# Diff_LPF.net
KiCad netlist of a schematic drawn in EAGLE
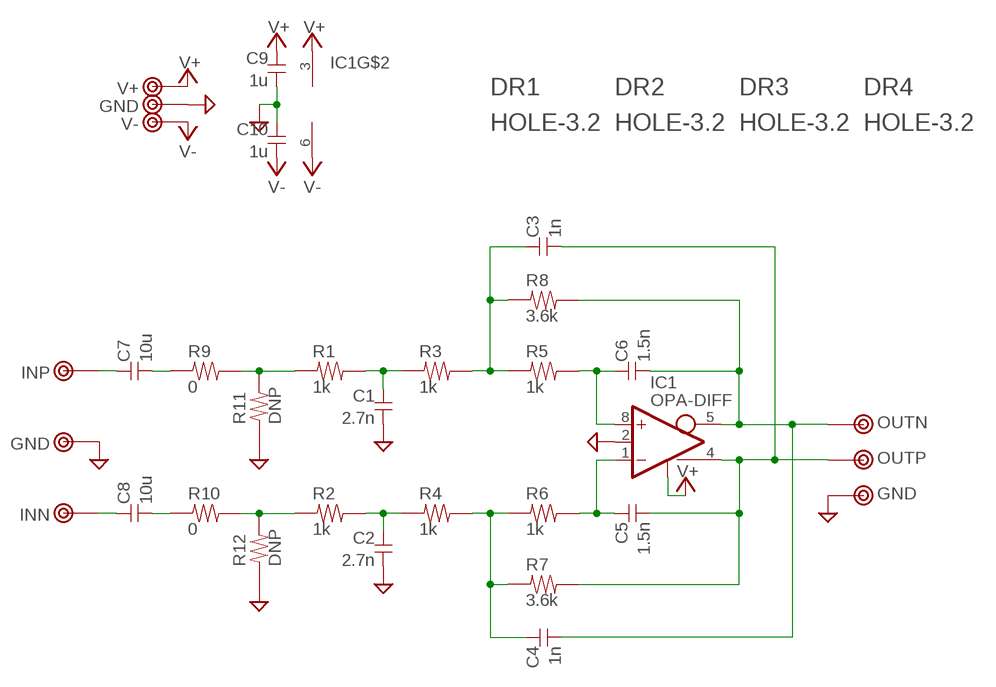
[diagram p0: schematic, sheet 1]

(export (version "E")
  (design (tool "Eeschema 10.0.6"))
  (components
    (comp (ref "C1")
      (value "2.7n")
      (footprint "eagle-import:1608C")
      (libsource (lib "eagle-import") (part "C-1608"))
    )
    (comp (ref "C2")
      (value "2.7n")
      (footprint "eagle-import:1608C")
      (libsource (lib "eagle-import") (part "C-1608"))
    )
    (comp (ref "C3")
      (value "1n")
      (footprint "eagle-import:1608C")
      (libsource (lib "eagle-import") (part "C-1608"))
    )
    (comp (ref "C4")
      (value "1n")
      (footprint "eagle-import:1608C")
      (libsource (lib "eagle-import") (part "C-1608"))
    )
    (comp (ref "C5")
      (value "1.5n")
      (footprint "eagle-import:1608C")
      (libsource (lib "eagle-import") (part "C-1608"))
    )
    (comp (ref "C6")
      (value "1.5n")
      (footprint "eagle-import:1608C")
      (libsource (lib "eagle-import") (part "C-1608"))
    )
    (comp (ref "C7")
      (value "10u")
      (footprint "eagle-import:C050W")
      (libsource (lib "eagle-import") (part "C-5W"))
    )
    (comp (ref "C8")
      (value "10u")
      (footprint "eagle-import:C050W")
      (libsource (lib "eagle-import") (part "C-5W"))
    )
    (comp (ref "C9")
      (value "1u")
      (footprint "eagle-import:1608C")
      (libsource (lib "eagle-import") (part "C-1608"))
    )
    (comp (ref "C10")
      (value "1u")
      (footprint "eagle-import:1608C")
      (libsource (lib "eagle-import") (part "C-1608"))
    )
    (comp (ref "DR1")
      (value "HOLE-3.2")
      (footprint "eagle-import:HOLE_3.2")
      (libsource (lib "eagle-import") (part "HOLE-3.2"))
    )
    (comp (ref "DR2")
      (value "HOLE-3.2")
      (footprint "eagle-import:HOLE_3.2")
      (libsource (lib "eagle-import") (part "HOLE-3.2"))
    )
    (comp (ref "DR3")
      (value "HOLE-3.2")
      (footprint "eagle-import:HOLE_3.2")
      (libsource (lib "eagle-import") (part "HOLE-3.2"))
    )
    (comp (ref "DR4")
      (value "HOLE-3.2")
      (footprint "eagle-import:HOLE_3.2")
      (libsource (lib "eagle-import") (part "HOLE-3.2"))
    )
    (comp (ref "IC1")
      (value "OPA-DIFF")
      (footprint "eagle-import:SOP8")
      (libsource (lib "eagle-import") (part "OPA-DIFF"))
    )
    (comp (ref "R1")
      (value "1k")
      (footprint "eagle-import:1608")
      (libsource (lib "eagle-import") (part "R-1608"))
    )
    (comp (ref "R2")
      (value "1k")
      (footprint "eagle-import:1608")
      (libsource (lib "eagle-import") (part "R-1608"))
    )
    (comp (ref "R3")
      (value "1k")
      (footprint "eagle-import:1608")
      (libsource (lib "eagle-import") (part "R-1608"))
    )
    (comp (ref "R4")
      (value "1k")
      (footprint "eagle-import:1608")
      (libsource (lib "eagle-import") (part "R-1608"))
    )
    (comp (ref "R5")
      (value "1k")
      (footprint "eagle-import:1608")
      (libsource (lib "eagle-import") (part "R-1608"))
    )
    (comp (ref "R6")
      (value "1k")
      (footprint "eagle-import:1608")
      (libsource (lib "eagle-import") (part "R-1608"))
    )
    (comp (ref "R7")
      (value "3.6k")
      (footprint "eagle-import:1608")
      (libsource (lib "eagle-import") (part "R-1608"))
    )
    (comp (ref "R8")
      (value "3.6k")
      (footprint "eagle-import:1608")
      (libsource (lib "eagle-import") (part "R-1608"))
    )
    (comp (ref "R9")
      (value "0")
      (footprint "eagle-import:1608")
      (libsource (lib "eagle-import") (part "R-1608"))
    )
    (comp (ref "R10")
      (value "0")
      (footprint "eagle-import:1608")
      (libsource (lib "eagle-import") (part "R-1608"))
    )
    (comp (ref "R11")
      (value "DNP")
      (footprint "eagle-import:1608")
      (libsource (lib "eagle-import") (part "R-1608"))
    )
    (comp (ref "R12")
      (value "DNP")
      (footprint "eagle-import:1608")
      (libsource (lib "eagle-import") (part "R-1608"))
    )
    (comp (ref "TP1")
      (value "INP")
      (footprint "eagle-import:TESTPIN-MID")
      (libsource (lib "eagle-import") (part "TESTPIN-MID"))
    )
    (comp (ref "TP2")
      (value "INN")
      (footprint "eagle-import:TESTPIN-MID")
      (libsource (lib "eagle-import") (part "TESTPIN-MID"))
    )
    (comp (ref "TP3")
      (value "OUTN")
      (footprint "eagle-import:TESTPIN-MID")
      (libsource (lib "eagle-import") (part "TESTPIN-MID"))
    )
    (comp (ref "TP4")
      (value "OUTP")
      (footprint "eagle-import:TESTPIN-MID")
      (libsource (lib "eagle-import") (part "TESTPIN-MID"))
    )
    (comp (ref "TP5")
      (value "V+")
      (footprint "eagle-import:TESTPIN-MID")
      (libsource (lib "eagle-import") (part "TESTPIN-MID"))
    )
    (comp (ref "TP6")
      (value "GND")
      (footprint "eagle-import:TESTPIN-MID")
      (libsource (lib "eagle-import") (part "TESTPIN-MID"))
    )
    (comp (ref "TP7")
      (value "V-")
      (footprint "eagle-import:TESTPIN-MID")
      (libsource (lib "eagle-import") (part "TESTPIN-MID"))
    )
    (comp (ref "TP8")
      (value "GND")
      (footprint "eagle-import:TESTPIN-MID")
      (libsource (lib "eagle-import") (part "TESTPIN-MID"))
    )
    (comp (ref "TP9")
      (value "GND")
      (footprint "eagle-import:TESTPIN-MID")
      (libsource (lib "eagle-import") (part "TESTPIN-MID"))
    )
  )
  (nets
    (net (code "1") (name "GND") (class "Default")
      (node (ref "C1") (pin "2") (pinfunction "2_2") (pintype "passive"))
      (node (ref "C10") (pin "1") (pinfunction "1_1") (pintype "passive"))
      (node (ref "C2") (pin "2") (pinfunction "2_2") (pintype "passive"))
      (node (ref "C9") (pin "2") (pinfunction "2_2") (pintype "passive"))
      (node (ref "IC1") (pin "2") (pinfunction "CM_2") (pintype "input"))
      (node (ref "R11") (pin "1") (pinfunction "1_1") (pintype "passive"))
      (node (ref "R12") (pin "1") (pinfunction "1_1") (pintype "passive"))
      (node (ref "TP6") (pin "1") (pinfunction "1_1") (pintype "passive"))
      (node (ref "TP8") (pin "1") (pinfunction "1_1") (pintype "passive"))
      (node (ref "TP9") (pin "1") (pinfunction "1_1") (pintype "passive"))
    )
    (net (code "2") (name "Net-(C1-Pad1)") (class "Default")
      (node (ref "C1") (pin "1") (pinfunction "1_1") (pintype "passive"))
      (node (ref "R1") (pin "2") (pinfunction "2_2") (pintype "passive"))
      (node (ref "R3") (pin "1") (pinfunction "1_1") (pintype "passive"))
    )
    (net (code "3") (name "Net-(C2-Pad1)") (class "Default")
      (node (ref "C2") (pin "1") (pinfunction "1_1") (pintype "passive"))
      (node (ref "R2") (pin "2") (pinfunction "2_2") (pintype "passive"))
      (node (ref "R4") (pin "1") (pinfunction "1_1") (pintype "passive"))
    )
    (net (code "4") (name "Net-(C3-Pad1)") (class "Default")
      (node (ref "C3") (pin "1") (pinfunction "1_1") (pintype "passive"))
      (node (ref "R3") (pin "2") (pinfunction "2_2") (pintype "passive"))
      (node (ref "R5") (pin "1") (pinfunction "1_1") (pintype "passive"))
      (node (ref "R8") (pin "1") (pinfunction "1_1") (pintype "passive"))
    )
    (net (code "5") (name "Net-(C4-Pad1)") (class "Default")
      (node (ref "C4") (pin "1") (pinfunction "1_1") (pintype "passive"))
      (node (ref "R4") (pin "2") (pinfunction "2_2") (pintype "passive"))
      (node (ref "R6") (pin "1") (pinfunction "1_1") (pintype "passive"))
      (node (ref "R7") (pin "1") (pinfunction "1_1") (pintype "passive"))
    )
    (net (code "6") (name "Net-(C7-1-Pad3)") (class "Default")
      (node (ref "C7") (pin "1") (pinfunction "1_1") (pintype "passive"))
      (node (ref "C7") (pin "3") (pinfunction "1_3") (pintype "passive"))
      (node (ref "TP1") (pin "1") (pinfunction "1_1") (pintype "passive"))
    )
    (net (code "7") (name "Net-(C7-2-Pad4)") (class "Default")
      (node (ref "C7") (pin "2") (pinfunction "2_2") (pintype "passive"))
      (node (ref "C7") (pin "4") (pinfunction "2_4") (pintype "passive"))
      (node (ref "R9") (pin "1") (pinfunction "1_1") (pintype "passive"))
    )
    (net (code "8") (name "Net-(C8-1-Pad3)") (class "Default")
      (node (ref "C8") (pin "1") (pinfunction "1_1") (pintype "passive"))
      (node (ref "C8") (pin "3") (pinfunction "1_3") (pintype "passive"))
      (node (ref "TP2") (pin "1") (pinfunction "1_1") (pintype "passive"))
    )
    (net (code "9") (name "Net-(C8-2-Pad4)") (class "Default")
      (node (ref "C8") (pin "2") (pinfunction "2_2") (pintype "passive"))
      (node (ref "C8") (pin "4") (pinfunction "2_4") (pintype "passive"))
      (node (ref "R10") (pin "1") (pinfunction "1_1") (pintype "passive"))
    )
    (net (code "10") (name "Net-(IC1A-+IN)") (class "Default")
      (node (ref "C6") (pin "1") (pinfunction "1_1") (pintype "passive"))
      (node (ref "IC1") (pin "8") (pinfunction "+IN_8") (pintype "input"))
      (node (ref "R5") (pin "2") (pinfunction "2_2") (pintype "passive"))
    )
    (net (code "11") (name "Net-(IC1A-+OUT)") (class "Default")
      (node (ref "C3") (pin "2") (pinfunction "2_2") (pintype "passive"))
      (node (ref "C5") (pin "2") (pinfunction "2_2") (pintype "passive"))
      (node (ref "IC1") (pin "4") (pinfunction "+OUT_4") (pintype "output"))
      (node (ref "R7") (pin "2") (pinfunction "2_2") (pintype "passive"))
      (node (ref "TP4") (pin "1") (pinfunction "1_1") (pintype "passive"))
    )
    (net (code "12") (name "Net-(IC1A--IN)") (class "Default")
      (node (ref "C5") (pin "1") (pinfunction "1_1") (pintype "passive"))
      (node (ref "IC1") (pin "1") (pinfunction "-IN_1") (pintype "input"))
      (node (ref "R6") (pin "2") (pinfunction "2_2") (pintype "passive"))
    )
    (net (code "13") (name "Net-(IC1A--OUT)") (class "Default")
      (node (ref "C4") (pin "2") (pinfunction "2_2") (pintype "passive"))
      (node (ref "C6") (pin "2") (pinfunction "2_2") (pintype "passive"))
      (node (ref "IC1") (pin "5") (pinfunction "-OUT_5") (pintype "output"))
      (node (ref "R8") (pin "2") (pinfunction "2_2") (pintype "passive"))
      (node (ref "TP3") (pin "1") (pinfunction "1_1") (pintype "passive"))
    )
    (net (code "14") (name "Net-(R1-Pad1)") (class "Default")
      (node (ref "R1") (pin "1") (pinfunction "1_1") (pintype "passive"))
      (node (ref "R11") (pin "2") (pinfunction "2_2") (pintype "passive"))
      (node (ref "R9") (pin "2") (pinfunction "2_2") (pintype "passive"))
    )
    (net (code "15") (name "Net-(R10-Pad2)") (class "Default")
      (node (ref "R10") (pin "2") (pinfunction "2_2") (pintype "passive"))
      (node (ref "R12") (pin "2") (pinfunction "2_2") (pintype "passive"))
      (node (ref "R2") (pin "1") (pinfunction "1_1") (pintype "passive"))
    )
    (net (code "16") (name "V+") (class "Default")
      (node (ref "C9") (pin "1") (pinfunction "1_1") (pintype "passive"))
      (node (ref "IC1") (pin "3") (pinfunction "V+_3") (pintype "input"))
      (node (ref "IC1") (pin "7") (pinfunction "EN_7") (pintype "bidirectional"))
      (node (ref "TP5") (pin "1") (pinfunction "1_1") (pintype "passive"))
    )
    (net (code "17") (name "V-") (class "Default")
      (node (ref "C10") (pin "2") (pinfunction "2_2") (pintype "passive"))
      (node (ref "IC1") (pin "6") (pinfunction "V-_6") (pintype "input"))
      (node (ref "TP7") (pin "1") (pinfunction "1_1") (pintype "passive"))
    )
  )
)
